# untitled.net
KiCad netlist of a schematic drawn in EAGLE
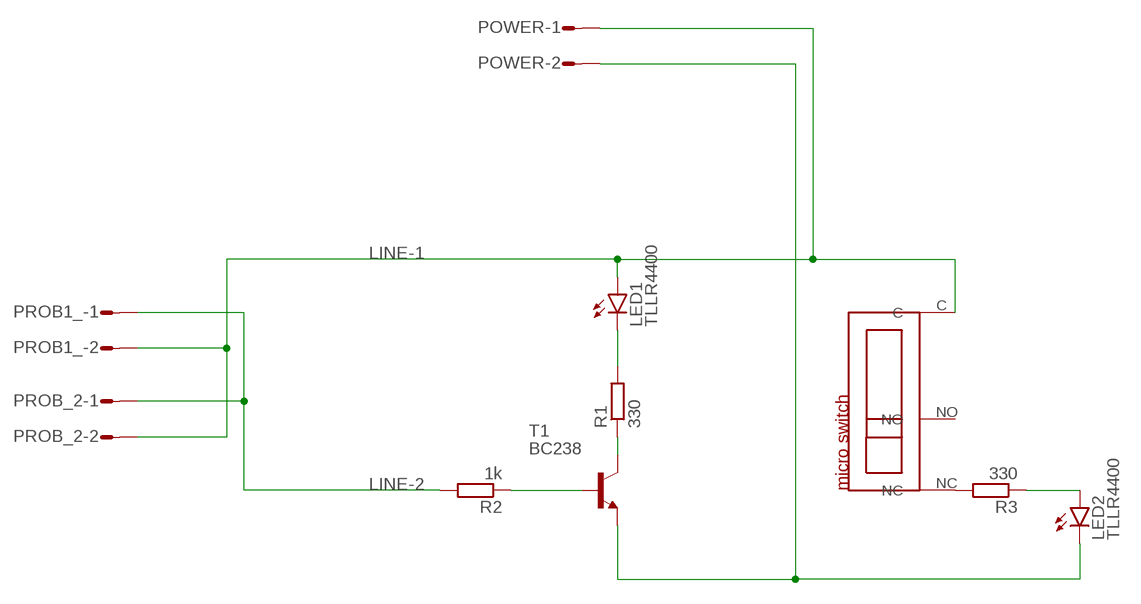
[diagram p0: schematic, sheet 1]

(export (version "E")
  (design (tool "Eeschema 10.0.6"))
  (components
    (comp (ref "LED1")
      (value "TLLR4400")
      (footprint "eagle-import:LED3MM")
      (fields (field (name "MF") "VISHAY SEMICONDUCTOR"))
      (libsource (lib "eagle-import") (part "TLLR4400"))
    )
    (comp (ref "LED2")
      (value "TLLR4400")
      (footprint "eagle-import:LED3MM")
      (fields (field (name "MF") "VISHAY SEMICONDUCTOR"))
      (libsource (lib "eagle-import") (part "TLLR4400"))
    )
    (comp (ref "POWER")
      (value "L02P")
      (footprint "eagle-import:L02P")
      (libsource (lib "eagle-import") (part "L02P"))
    )
    (comp (ref "PROB1_")
      (value "L02P")
      (footprint "eagle-import:L02P")
      (libsource (lib "eagle-import") (part "L02P"))
    )
    (comp (ref "PROB_2")
      (value "L02P")
      (footprint "eagle-import:L02P")
      (libsource (lib "eagle-import") (part "L02P"))
    )
    (comp (ref "R1")
      (value "330")
      (footprint "eagle-import:0204_7")
      (libsource (lib "eagle-import") (part "R-EU_0204/7"))
    )
    (comp (ref "R2")
      (value "1k")
      (footprint "eagle-import:0204_7")
      (libsource (lib "eagle-import") (part "R-EU_0204/7"))
    )
    (comp (ref "R3")
      (value "330")
      (footprint "eagle-import:0204_7")
      (libsource (lib "eagle-import") (part "R-EU_0204/7"))
    )
    (comp (ref "T1")
      (value "BC238")
      (footprint "eagle-import:TO92")
      (libsource (lib "eagle-import") (part "BC238"))
    )
    (comp (ref "U$1")
      (value "MICRO_SWITCH")
      (footprint "eagle-import:MICRO_SWITCH")
      (libsource (lib "eagle-import") (part "MICRO_SWITCH"))
    )
  )
  (nets
    (net (code "1") (name "/LINE-1") (class "Default")
      (node (ref "LED1") (pin "A") (pinfunction "A_A") (pintype "passive"))
      (node (ref "POWER") (pin "1") (pinfunction "S_1") (pintype "passive"))
      (node (ref "PROB1_") (pin "2") (pinfunction "S_2") (pintype "passive"))
      (node (ref "PROB_2") (pin "2") (pinfunction "S_2") (pintype "passive"))
      (node (ref "U$1") (pin "C") (pinfunction "C_C") (pintype "bidirectional"))
    )
    (net (code "2") (name "/LINE-2") (class "Default")
      (node (ref "PROB1_") (pin "1") (pinfunction "S_1") (pintype "passive"))
      (node (ref "PROB_2") (pin "1") (pinfunction "S_1") (pintype "passive"))
      (node (ref "R2") (pin "2") (pinfunction "2_2") (pintype "passive"))
    )
    (net (code "3") (name "Net-(LED1-C)") (class "Default")
      (node (ref "LED1") (pin "K") (pinfunction "C_K") (pintype "passive"))
      (node (ref "R1") (pin "2") (pinfunction "2_2") (pintype "passive"))
    )
    (net (code "4") (name "Net-(LED2-C)") (class "Default")
      (node (ref "LED2") (pin "K") (pinfunction "C_K") (pintype "passive"))
      (node (ref "POWER") (pin "2") (pinfunction "S_2") (pintype "passive"))
      (node (ref "T1") (pin "1") (pinfunction "E_1") (pintype "passive"))
    )
    (net (code "5") (name "Net-(LED2-PadA)") (class "Default")
      (node (ref "LED2") (pin "A") (pinfunction "A_A") (pintype "passive"))
      (node (ref "R3") (pin "1") (pinfunction "1_1") (pintype "passive"))
    )
    (net (code "6") (name "Net-(R3-Pad2)") (class "Default")
      (node (ref "R3") (pin "2") (pinfunction "2_2") (pintype "passive"))
      (node (ref "U$1") (pin "NC") (pinfunction "NC_NC") (pintype "bidirectional"))
    )
    (net (code "7") (name "Net-(T1-B)") (class "Default")
      (node (ref "R2") (pin "1") (pinfunction "1_1") (pintype "passive"))
      (node (ref "T1") (pin "2") (pinfunction "B_2") (pintype "passive"))
    )
    (net (code "8") (name "Net-(T1-C)") (class "Default")
      (node (ref "R1") (pin "1") (pinfunction "1_1") (pintype "passive"))
      (node (ref "T1") (pin "3") (pinfunction "C_3") (pintype "passive"))
    )
    (net (code "9") (name "unconnected-(U$1-PadNO)") (class "Default")
      (node (ref "U$1") (pin "NO") (pinfunction "NO_NO") (pintype "bidirectional"))
    )
  )
)
